# clock-kit-board.net
KiCad netlist of a schematic drawn in EAGLE
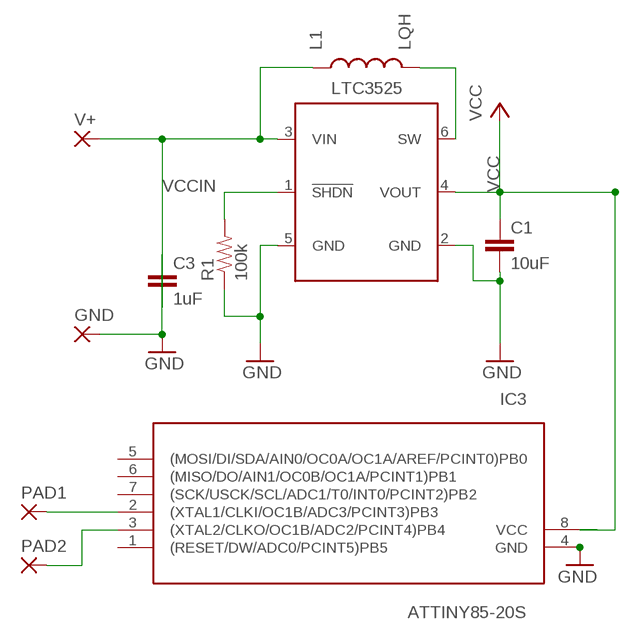
[diagram p0: schematic, sheet 1]

(export (version "E")
  (design (tool "Eeschema 10.0.6"))
  (components
    (comp (ref "C1")
      (value "10uF")
      (footprint "eagle-import:0805")
      (libsource (lib "eagle-import") (part "CAP0805"))
    )
    (comp (ref "C3")
      (value "1uF")
      (footprint "eagle-import:0805")
      (libsource (lib "eagle-import") (part "CAP0805"))
    )
    (comp (ref "GND")
      (value "SMD5")
      (footprint "eagle-import:SMD2,54-5,08")
      (libsource (lib "eagle-import") (part "SMD5"))
    )
    (comp (ref "IC3")
      (value "ATTINY85-20S")
      (footprint "eagle-import:SOIC8")
      (libsource (lib "eagle-import") (part "ATTINY85SV-10"))
    )
    (comp (ref "L1")
      (value "LQH")
      (footprint "eagle-import:LQH32")
      (libsource (lib "eagle-import") (part "LQH"))
    )
    (comp (ref "PAD1")
      (value "2,54/1,1")
      (footprint "eagle-import:2,54_1,1")
      (libsource (lib "eagle-import") (part "2,54/1,1"))
    )
    (comp (ref "PAD2")
      (value "2,54/1,1")
      (footprint "eagle-import:2,54_1,1")
      (libsource (lib "eagle-import") (part "2,54/1,1"))
    )
    (comp (ref "R1")
      (value "100k")
      (footprint "eagle-import:0805")
      (libsource (lib "eagle-import") (part "RESISTOR0805-RES"))
    )
    (comp (ref "U1")
      (value "LTC3525")
      (footprint "eagle-import:SC70-6L")
      (libsource (lib "eagle-import") (part "LTC3525"))
    )
    (comp (ref "V+")
      (value "SMD5")
      (footprint "eagle-import:SMD2,54-5,08")
      (libsource (lib "eagle-import") (part "SMD5"))
    )
  )
  (nets
    (net (code "1") (name "/VCCIN") (class "Default")
      (node (ref "C3") (pin "2") (pinfunction "2_2") (pintype "passive"))
      (node (ref "L1") (pin "1") (pinfunction "1_1") (pintype "passive"))
      (node (ref "U1") (pin "3") (pinfunction "VIN_3") (pintype "input"))
      (node (ref "V+") (pin "1") (pinfunction "P_1") (pintype "passive"))
    )
    (net (code "2") (name "GND") (class "Default")
      (node (ref "C1") (pin "2") (pinfunction "2_2") (pintype "passive"))
      (node (ref "C3") (pin "1") (pinfunction "1_1") (pintype "passive"))
      (node (ref "GND") (pin "1") (pinfunction "P_1") (pintype "passive"))
      (node (ref "IC3") (pin "4") (pinfunction "GND_4") (pintype "bidirectional"))
      (node (ref "R1") (pin "1") (pinfunction "1_1") (pintype "passive"))
      (node (ref "U1") (pin "2") (pinfunction "GND_2") (pintype "power_in"))
      (node (ref "U1") (pin "5") (pinfunction "GND_5") (pintype "input"))
    )
    (net (code "3") (name "Net-(IC3-(XTAL1{slash}CLKI{slash}OC1B{slash}ADC3{slash}PCINT3)PB3)") (class "Default")
      (node (ref "IC3") (pin "2") (pinfunction "(XTAL1/CLKI/OC1B/ADC3/PCINT3)PB3_2") (pintype "bidirectional"))
      (node (ref "PAD1") (pin "1") (pinfunction "P_1") (pintype "passive"))
    )
    (net (code "4") (name "Net-(IC3-(XTAL2{slash}CLKO{slash}OC1B{slash}ADC2{slash}PCINT4)PB4)") (class "Default")
      (node (ref "IC3") (pin "3") (pinfunction "(XTAL2/CLKO/OC1B/ADC2/PCINT4)PB4_3") (pintype "bidirectional"))
      (node (ref "PAD2") (pin "1") (pinfunction "P_1") (pintype "passive"))
    )
    (net (code "5") (name "Net-(U1-SW)") (class "Default")
      (node (ref "L1") (pin "2") (pinfunction "2_2") (pintype "passive"))
      (node (ref "U1") (pin "6") (pinfunction "SW_6") (pintype "passive"))
    )
    (net (code "6") (name "Net-(U1-~{SHDN})") (class "Default")
      (node (ref "R1") (pin "2") (pinfunction "2_2") (pintype "passive"))
      (node (ref "U1") (pin "1") (pinfunction "~{SHDN}_1") (pintype "passive"))
    )
    (net (code "7") (name "VCC") (class "Default")
      (node (ref "C1") (pin "1") (pinfunction "1_1") (pintype "passive"))
      (node (ref "IC3") (pin "8") (pinfunction "VCC_8") (pintype "bidirectional"))
      (node (ref "U1") (pin "4") (pinfunction "VOUT_4") (pintype "passive"))
    )
    (net (code "8") (name "unconnected-(IC3-(MISO{slash}DO{slash}AIN1{slash}OC0B{slash}OC1A{slash}PCINT1)PB1-Pad6)") (class "Default")
      (node (ref "IC3") (pin "6") (pinfunction "(MISO/DO/AIN1/OC0B/OC1A/PCINT1)PB1_6") (pintype "bidirectional"))
    )
    (net (code "9") (name "unconnected-(IC3-(MOSI{slash}DI{slash}SDA{slash}AIN0{slash}OC0A{slash}OC1A{slash}AREF{slash}PCINT0)PB0-Pad5)") (class "Default")
      (node (ref "IC3") (pin "5") (pinfunction "(MOSI/DI/SDA/AIN0/OC0A/OC1A/AREF/PCINT0)PB0_5") (pintype "bidirectional"))
    )
    (net (code "10") (name "unconnected-(IC3-(RESET{slash}DW{slash}ADC0{slash}PCINT5)PB5-Pad1)") (class "Default")
      (node (ref "IC3") (pin "1") (pinfunction "(RESET/DW/ADC0/PCINT5)PB5_1") (pintype "bidirectional"))
    )
    (net (code "11") (name "unconnected-(IC3-(SCK{slash}USCK{slash}SCL{slash}ADC1{slash}T0{slash}INT0{slash}PCINT2)PB2-Pad7)") (class "Default")
      (node (ref "IC3") (pin "7") (pinfunction "(SCK/USCK/SCL/ADC1/T0/INT0/PCINT2)PB2_7") (pintype "bidirectional"))
    )
  )
)
